# 101_Power.net
KiCad netlist of a schematic drawn in Altium Designer
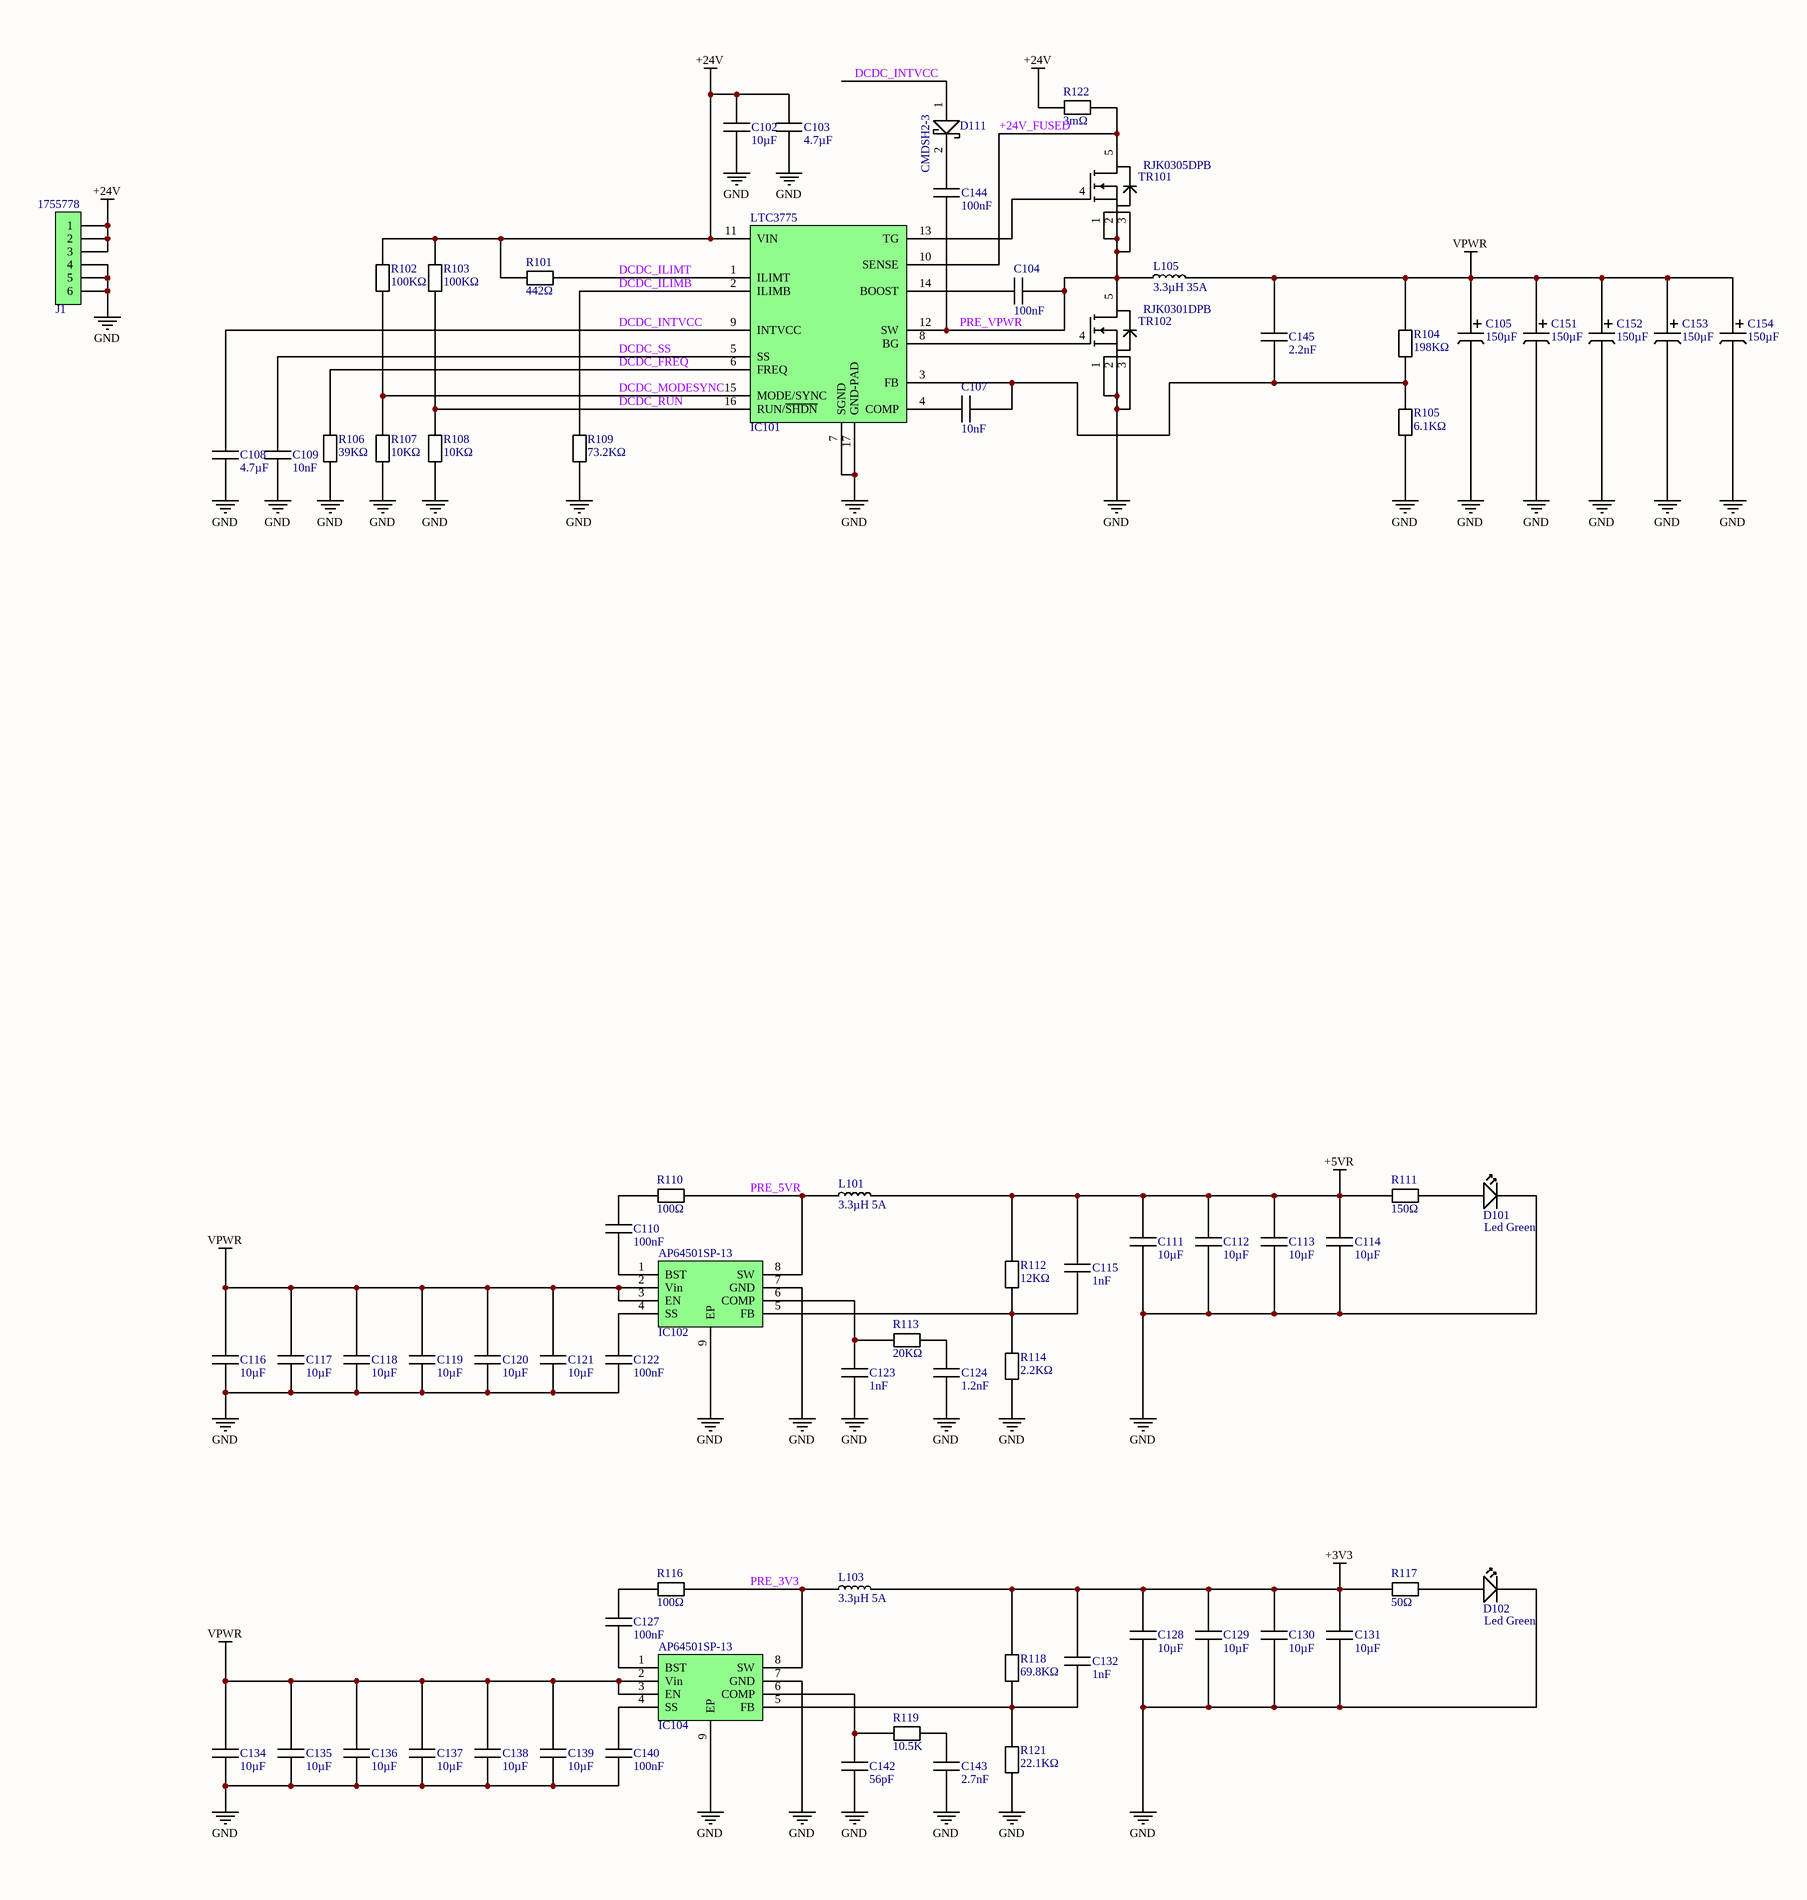
[diagram p0: 101_Power.SchDoc, left]
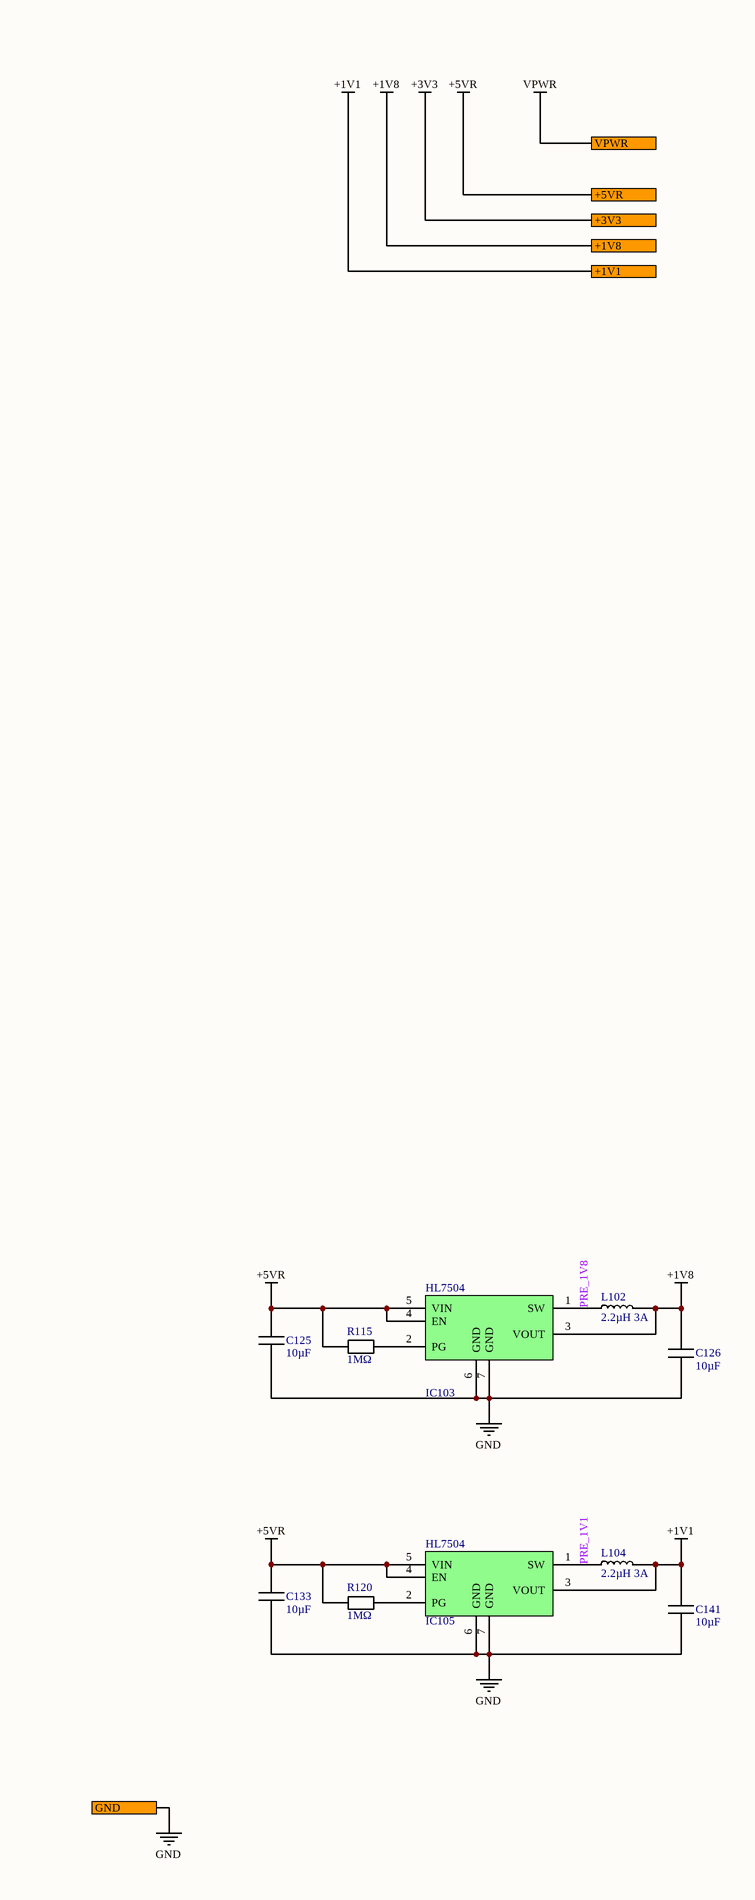
[diagram p1: 101_Power.SchDoc, right]

(export (version "E")
  (design (tool "Eeschema 10.0.6"))
  (components
    (comp (ref "C102")
      (value "10µF")
      (footprint "C1210")
      (description "10µF 63V 10% X7R")
      (fields
        (field (name "REFVAL") "10µF")
        (field (name "PART NUMBER") "CA0024")
        (field (name "MANFACTPART") "GRM32ER71J106KA12")
      )
      (libsource (lib "GTS_Database") (part "C"))
    )
    (comp (ref "C103")
      (value "4.7µF")
      (footprint "C1210")
      (description "4.7µF 100V 10% X5R")
      (fields
        (field (name "REFVAL") "4.7µF")
        (field (name "PART NUMBER") "CA0038")
        (field (name "MANFACTPART") "HMK325BJ475KM-PE")
      )
      (libsource (lib "GTS_Database") (part "C"))
    )
    (comp (ref "C104")
      (value "100nF")
      (footprint "C0402")
      (description "100nF 50V 10% X7R")
      (fields
        (field (name "REFVAL") "100nF")
        (field (name "PART NUMBER") "CA0029")
        (field (name "MANFACTPART") "CGA2B3X7R1H104K050BB")
      )
      (libsource (lib "GTS_Database") (part "C"))
    )
    (comp (ref "C105")
      (value "150µF")
      (footprint "Tantalum_2924_4.1MM")
      (description "150µF 35V 20% 100mΩ")
      (fields
        (field (name "REFVAL") "150µF")
        (field (name "PART NUMBER") "CA0076")
        (field (name "MANFACTPART") "TCJU157M035R0100E")
      )
      (libsource (lib "GTS_Database") (part "C+"))
    )
    (comp (ref "C107")
      (value "10nF")
      (footprint "C0805")
      (description "10nF 50V 10% X7R")
      (fields
        (field (name "REFVAL") "10nF")
        (field (name "PART NUMBER") "CA0021")
        (field (name "MANFACTPART") "C0805C103K5RAC")
      )
      (libsource (lib "GTS_Database") (part "C"))
    )
    (comp (ref "C108")
      (value "4.7µF")
      (footprint "C1210")
      (description "4.7µF 100V 10% X5R")
      (fields
        (field (name "REFVAL") "4.7µF")
        (field (name "PART NUMBER") "CA0038")
        (field (name "MANFACTPART") "HMK325BJ475KM-PE")
      )
      (libsource (lib "GTS_Database") (part "C"))
    )
    (comp (ref "C109")
      (value "10nF")
      (footprint "C0805")
      (description "10nF 50V 10% X7R")
      (fields
        (field (name "REFVAL") "10nF")
        (field (name "PART NUMBER") "CA0021")
        (field (name "MANFACTPART") "C0805C103K5RAC")
      )
      (libsource (lib "GTS_Database") (part "C"))
    )
    (comp (ref "C110")
      (value "100nF")
      (footprint "C0402")
      (description "100nF 50V 10% X7R")
      (fields
        (field (name "REFVAL") "100nF")
        (field (name "PART NUMBER") "CA0029")
        (field (name "MANFACTPART") "CGA2B3X7R1H104K050BB")
      )
      (libsource (lib "GTS_Database") (part "C"))
    )
    (comp (ref "C111")
      (value "10µF")
      (footprint "C0805")
      (description "10µF 16V 10% X5R")
      (fields
        (field (name "REFVAL") "10µF")
        (field (name "PART NUMBER") "CA0001")
        (field (name "MANFACTPART") "GRM21BR61C106KE15L")
      )
      (libsource (lib "GTS_Database") (part "C"))
    )
    (comp (ref "C112")
      (value "10µF")
      (footprint "C0805")
      (description "10µF 16V 10% X5R")
      (fields
        (field (name "REFVAL") "10µF")
        (field (name "PART NUMBER") "CA0001")
        (field (name "MANFACTPART") "GRM21BR61C106KE15L")
      )
      (libsource (lib "GTS_Database") (part "C"))
    )
    (comp (ref "C113")
      (value "10µF")
      (footprint "C0805")
      (description "10µF 16V 10% X5R")
      (fields
        (field (name "REFVAL") "10µF")
        (field (name "PART NUMBER") "CA0001")
        (field (name "MANFACTPART") "GRM21BR61C106KE15L")
      )
      (libsource (lib "GTS_Database") (part "C"))
    )
    (comp (ref "C114")
      (value "10µF")
      (footprint "C0805")
      (description "10µF 16V 10% X5R")
      (fields
        (field (name "REFVAL") "10µF")
        (field (name "PART NUMBER") "CA0001")
        (field (name "MANFACTPART") "GRM21BR61C106KE15L")
      )
      (libsource (lib "GTS_Database") (part "C"))
    )
    (comp (ref "C115")
      (value "1nF")
      (footprint "C0402")
      (description "1nF 50V 1% C0G")
      (fields
        (field (name "REFVAL") "1nF")
        (field (name "PART NUMBER") "CA0031")
        (field (name "MANFACTPART") "GRT1555C1H102FA02D")
      )
      (libsource (lib "GTS_Database") (part "C"))
    )
    (comp (ref "C116")
      (value "10µF")
      (footprint "C0805")
      (description "10µF 35V 10% X5R")
      (fields
        (field (name "REFVAL") "10µF")
        (field (name "PART NUMBER") "CA0005")
        (field (name "MANFACTPART") "C2012X5R1V106K125AC")
      )
      (libsource (lib "GTS_Database") (part "C"))
    )
    (comp (ref "C117")
      (value "10µF")
      (footprint "C0805")
      (description "10µF 35V 10% X5R")
      (fields
        (field (name "REFVAL") "10µF")
        (field (name "PART NUMBER") "CA0005")
        (field (name "MANFACTPART") "C2012X5R1V106K125AC")
      )
      (libsource (lib "GTS_Database") (part "C"))
    )
    (comp (ref "C118")
      (value "10µF")
      (footprint "C0805")
      (description "10µF 35V 10% X5R")
      (fields
        (field (name "REFVAL") "10µF")
        (field (name "PART NUMBER") "CA0005")
        (field (name "MANFACTPART") "C2012X5R1V106K125AC")
      )
      (libsource (lib "GTS_Database") (part "C"))
    )
    (comp (ref "C119")
      (value "10µF")
      (footprint "C0805")
      (description "10µF 35V 10% X5R")
      (fields
        (field (name "REFVAL") "10µF")
        (field (name "PART NUMBER") "CA0005")
        (field (name "MANFACTPART") "C2012X5R1V106K125AC")
      )
      (libsource (lib "GTS_Database") (part "C"))
    )
    (comp (ref "C120")
      (value "10µF")
      (footprint "C0805")
      (description "10µF 35V 10% X5R")
      (fields
        (field (name "REFVAL") "10µF")
        (field (name "PART NUMBER") "CA0005")
        (field (name "MANFACTPART") "C2012X5R1V106K125AC")
      )
      (libsource (lib "GTS_Database") (part "C"))
    )
    (comp (ref "C121")
      (value "10µF")
      (footprint "C0805")
      (description "10µF 35V 10% X5R")
      (fields
        (field (name "REFVAL") "10µF")
        (field (name "PART NUMBER") "CA0005")
        (field (name "MANFACTPART") "C2012X5R1V106K125AC")
      )
      (libsource (lib "GTS_Database") (part "C"))
    )
    (comp (ref "C122")
      (value "100nF")
      (footprint "C0402")
      (description "100nF 50V 10% X7R")
      (fields
        (field (name "REFVAL") "100nF")
        (field (name "PART NUMBER") "CA0029")
        (field (name "MANFACTPART") "CGA2B3X7R1H104K050BB")
      )
      (libsource (lib "GTS_Database") (part "C"))
    )
    (comp (ref "C123")
      (value "1nF")
      (footprint "C0402")
      (description "1nF 50V 1% C0G")
      (fields
        (field (name "REFVAL") "1nF")
        (field (name "PART NUMBER") "CA0031")
        (field (name "MANFACTPART") "GRT1555C1H102FA02D")
      )
      (libsource (lib "GTS_Database") (part "C"))
    )
    (comp (ref "C124")
      (value "1.2nF")
      (footprint "C0402")
      (description "1.2nF 50V 10% X7R")
      (fields
        (field (name "REFVAL") "1.2nF")
        (field (name "PART NUMBER") "CA0030")
        (field (name "MANFACTPART") "GCM155R71H122KA37D")
      )
      (libsource (lib "GTS_Database") (part "C"))
    )
    (comp (ref "C125")
      (value "10µF")
      (footprint "C0603")
      (description "10µF 16V 20% X5R")
      (fields
        (field (name "REFVAL") "10µF")
        (field (name "PART NUMBER") "CA0008")
        (field (name "MANFACTPART") "GRM188R61C106MAALD")
      )
      (libsource (lib "GTS_Database") (part "C"))
    )
    (comp (ref "C126")
      (value "10µF")
      (footprint "C0603")
      (description "10µF 16V 20% X5R")
      (fields
        (field (name "REFVAL") "10µF")
        (field (name "PART NUMBER") "CA0008")
        (field (name "MANFACTPART") "GRM188R61C106MAALD")
      )
      (libsource (lib "GTS_Database") (part "C"))
    )
    (comp (ref "C127")
      (value "100nF")
      (footprint "C0402")
      (description "100nF 50V 10% X7R")
      (fields
        (field (name "REFVAL") "100nF")
        (field (name "PART NUMBER") "CA0029")
        (field (name "MANFACTPART") "CGA2B3X7R1H104K050BB")
      )
      (libsource (lib "GTS_Database") (part "C"))
    )
    (comp (ref "C128")
      (value "10µF")
      (footprint "C0805")
      (description "10µF 16V 10% X5R")
      (fields
        (field (name "REFVAL") "10µF")
        (field (name "PART NUMBER") "CA0001")
        (field (name "MANFACTPART") "GRM21BR61C106KE15L")
      )
      (libsource (lib "GTS_Database") (part "C"))
    )
    (comp (ref "C129")
      (value "10µF")
      (footprint "C0805")
      (description "10µF 16V 10% X5R")
      (fields
        (field (name "REFVAL") "10µF")
        (field (name "PART NUMBER") "CA0001")
        (field (name "MANFACTPART") "GRM21BR61C106KE15L")
      )
      (libsource (lib "GTS_Database") (part "C"))
    )
    (comp (ref "C130")
      (value "10µF")
      (footprint "C0805")
      (description "10µF 16V 10% X5R")
      (fields
        (field (name "REFVAL") "10µF")
        (field (name "PART NUMBER") "CA0001")
        (field (name "MANFACTPART") "GRM21BR61C106KE15L")
      )
      (libsource (lib "GTS_Database") (part "C"))
    )
    (comp (ref "C131")
      (value "10µF")
      (footprint "C0805")
      (description "10µF 16V 10% X5R")
      (fields
        (field (name "REFVAL") "10µF")
        (field (name "PART NUMBER") "CA0001")
        (field (name "MANFACTPART") "GRM21BR61C106KE15L")
      )
      (libsource (lib "GTS_Database") (part "C"))
    )
    (comp (ref "C132")
      (value "1nF")
      (footprint "C0402")
      (description "1nF 50V 1% C0G")
      (fields
        (field (name "REFVAL") "1nF")
        (field (name "PART NUMBER") "CA0031")
        (field (name "MANFACTPART") "GRT1555C1H102FA02D")
      )
      (libsource (lib "GTS_Database") (part "C"))
    )
    (comp (ref "C133")
      (value "10µF")
      (footprint "C0603")
      (description "10µF 16V 20% X5R")
      (fields
        (field (name "REFVAL") "10µF")
        (field (name "PART NUMBER") "CA0008")
        (field (name "MANFACTPART") "GRM188R61C106MAALD")
      )
      (libsource (lib "GTS_Database") (part "C"))
    )
    (comp (ref "C134")
      (value "10µF")
      (footprint "C0805")
      (description "10µF 35V 10% X5R")
      (fields
        (field (name "REFVAL") "10µF")
        (field (name "PART NUMBER") "CA0005")
        (field (name "MANFACTPART") "C2012X5R1V106K125AC")
      )
      (libsource (lib "GTS_Database") (part "C"))
    )
    (comp (ref "C135")
      (value "10µF")
      (footprint "C0805")
      (description "10µF 35V 10% X5R")
      (fields
        (field (name "REFVAL") "10µF")
        (field (name "PART NUMBER") "CA0005")
        (field (name "MANFACTPART") "C2012X5R1V106K125AC")
      )
      (libsource (lib "GTS_Database") (part "C"))
    )
    (comp (ref "C136")
      (value "10µF")
      (footprint "C0805")
      (description "10µF 35V 10% X5R")
      (fields
        (field (name "REFVAL") "10µF")
        (field (name "PART NUMBER") "CA0005")
        (field (name "MANFACTPART") "C2012X5R1V106K125AC")
      )
      (libsource (lib "GTS_Database") (part "C"))
    )
    (comp (ref "C137")
      (value "10µF")
      (footprint "C0805")
      (description "10µF 35V 10% X5R")
      (fields
        (field (name "REFVAL") "10µF")
        (field (name "PART NUMBER") "CA0005")
        (field (name "MANFACTPART") "C2012X5R1V106K125AC")
      )
      (libsource (lib "GTS_Database") (part "C"))
    )
    (comp (ref "C138")
      (value "10µF")
      (footprint "C0805")
      (description "10µF 35V 10% X5R")
      (fields
        (field (name "REFVAL") "10µF")
        (field (name "PART NUMBER") "CA0005")
        (field (name "MANFACTPART") "C2012X5R1V106K125AC")
      )
      (libsource (lib "GTS_Database") (part "C"))
    )
    (comp (ref "C139")
      (value "10µF")
      (footprint "C0805")
      (description "10µF 35V 10% X5R")
      (fields
        (field (name "REFVAL") "10µF")
        (field (name "PART NUMBER") "CA0005")
        (field (name "MANFACTPART") "C2012X5R1V106K125AC")
      )
      (libsource (lib "GTS_Database") (part "C"))
    )
    (comp (ref "C140")
      (value "100nF")
      (footprint "C0402")
      (description "100nF 50V 10% X7R")
      (fields
        (field (name "REFVAL") "100nF")
        (field (name "PART NUMBER") "CA0029")
        (field (name "MANFACTPART") "CGA2B3X7R1H104K050BB")
      )
      (libsource (lib "GTS_Database") (part "C"))
    )
    (comp (ref "C141")
      (value "10µF")
      (footprint "C0603")
      (description "10µF 16V 20% X5R")
      (fields
        (field (name "REFVAL") "10µF")
        (field (name "PART NUMBER") "CA0008")
        (field (name "MANFACTPART") "GRM188R61C106MAALD")
      )
      (libsource (lib "GTS_Database") (part "C"))
    )
    (comp (ref "C142")
      (value "56pF")
      (footprint "C0402")
      (description "56pF 50V 2% C0G")
      (fields
        (field (name "REFVAL") "56pF")
        (field (name "PART NUMBER") "CA0068")
        (field (name "MANFACTPART") "CC0402GRNPO9BN560")
      )
      (libsource (lib "GTS_Database") (part "C"))
    )
    (comp (ref "C143")
      (value "2.7nF")
      (footprint "C0402")
      (description "2.7nF 50V 5% X7R")
      (fields
        (field (name "REFVAL") "2.7nF")
        (field (name "PART NUMBER") "CA0055")
        (field (name "MANFACTPART") "GRM155R71H272JA01D")
      )
      (libsource (lib "GTS_Database") (part "C"))
    )
    (comp (ref "C144")
      (value "100nF")
      (footprint "C0402")
      (description "100nF 50V 10% X7R")
      (fields
        (field (name "REFVAL") "100nF")
        (field (name "PART NUMBER") "CA0029")
        (field (name "MANFACTPART") "CGA2B3X7R1H104K050BB")
      )
      (libsource (lib "GTS_Database") (part "C"))
    )
    (comp (ref "C145")
      (value "2.2nF")
      (footprint "C0805")
      (description "2.2nF 50V 10% X7R")
      (fields
        (field (name "REFVAL") "2.2nF")
        (field (name "PART NUMBER") "CA0070")
        (field (name "MANFACTPART") "C0805C222K5RAC")
      )
      (libsource (lib "GTS_Database") (part "C"))
    )
    (comp (ref "C151")
      (value "150µF")
      (footprint "Tantalum_2924_4.1MM")
      (description "150µF 35V 20% 100mΩ")
      (fields
        (field (name "REFVAL") "150µF")
        (field (name "PART NUMBER") "CA0076")
        (field (name "MANFACTPART") "TCJU157M035R0100E")
      )
      (libsource (lib "GTS_Database") (part "C+"))
    )
    (comp (ref "C152")
      (value "150µF")
      (footprint "Tantalum_2924_4.1MM")
      (description "150µF 35V 20% 100mΩ")
      (fields
        (field (name "REFVAL") "150µF")
        (field (name "PART NUMBER") "CA0076")
        (field (name "MANFACTPART") "TCJU157M035R0100E")
      )
      (libsource (lib "GTS_Database") (part "C+"))
    )
    (comp (ref "C153")
      (value "150µF")
      (footprint "Tantalum_2924_4.1MM")
      (description "150µF 35V 20% 100mΩ")
      (fields
        (field (name "REFVAL") "150µF")
        (field (name "PART NUMBER") "CA0076")
        (field (name "MANFACTPART") "TCJU157M035R0100E")
      )
      (libsource (lib "GTS_Database") (part "C+"))
    )
    (comp (ref "C154")
      (value "150µF")
      (footprint "Tantalum_2924_4.1MM")
      (description "150µF 35V 20% 100mΩ")
      (fields
        (field (name "REFVAL") "150µF")
        (field (name "PART NUMBER") "CA0076")
        (field (name "MANFACTPART") "TCJU157M035R0100E")
      )
      (libsource (lib "GTS_Database") (part "C+"))
    )
    (comp (ref "D101")
      (value "Led Green")
      (footprint "Led0805")
      (fields
        (field (name "REFVAL") "Led Green")
        (field (name "PART NUMBER") "DI0001")
        (field (name "MANFACTPART") "KP-2012CGCK")
      )
      (libsource (lib "GTS_Database") (part "Led"))
    )
    (comp (ref "D102")
      (value "Led Green")
      (footprint "Led0805")
      (fields
        (field (name "REFVAL") "Led Green")
        (field (name "PART NUMBER") "DI0001")
        (field (name "MANFACTPART") "KP-2012CGCK")
      )
      (libsource (lib "GTS_Database") (part "Led"))
    )
    (comp (ref "D111")
      (value "CMDSH2-3")
      (footprint "SOD-323")
      (description "Schottky Diodes 30V")
      (fields
        (field (name "REFVAL") "CMDSH2-3")
        (field (name "PART NUMBER") "DI0013")
        (field (name "MANFACTPART") "CMDSH2-3 TR PBFREE")
      )
      (libsource (lib "GTS_Database") (part "Dschottky"))
    )
    (comp (ref "IC101")
      (value "LTC3775")
      (footprint "QFN-16G_3X3")
      (description "High Frequency Synchronous Step-Down Voltage Mode DC/DC Controller")
      (fields
        (field (name "REFVAL") "LTC3775")
        (field (name "PART NUMBER") "IC0063")
        (field (name "MANFACTPART") "LTC3775IUD#PBF")
      )
      (libsource (lib "GTS_Database") (part "LTC3775"))
    )
    (comp (ref "IC102")
      (value "AP64501SP-13")
      (footprint "SO-8-EP")
      (description "3.8V TO 40V INPUT, 5A LOW IQ SYNCHRONOUS BUCK WITH PROGRAMMABLE SOFT-START TIME")
      (fields (field (name "REFVAL") "AP64501SP-13") (field (name "PART NUMBER") "IC0031"))
      (libsource (lib "GTS_Database") (part "AP645"))
    )
    (comp (ref "IC103")
      (value "HL7504")
      (footprint "DFN-6G_2X2")
      (description "3MHz 2A Buck Converter 1.80V OUT")
      (fields
        (field (name "REFVAL") "HL7504")
        (field (name "PART NUMBER") "IC0064")
        (field (name "MANFACTPART") "HL7504FN07")
      )
      (libsource (lib "GTS_Database") (part "HL7504"))
    )
    (comp (ref "IC104")
      (value "AP64501SP-13")
      (footprint "SO-8-EP")
      (description "3.8V TO 40V INPUT, 5A LOW IQ SYNCHRONOUS BUCK WITH PROGRAMMABLE SOFT-START TIME")
      (fields (field (name "REFVAL") "AP64501SP-13") (field (name "PART NUMBER") "IC0031"))
      (libsource (lib "GTS_Database") (part "AP645"))
    )
    (comp (ref "IC105")
      (value "HL7504")
      (footprint "DFN-6G_2X2")
      (description "3MHz 2A Buck Converter 1.10V OUT")
      (fields
        (field (name "REFVAL") "HL7504")
        (field (name "PART NUMBER") "IC0050")
        (field (name "MANFACTPART") "HL7504FN08")
      )
      (libsource (lib "GTS_Database") (part "HL7504"))
    )
    (comp (ref "J1")
      (value "1755778")
      (footprint "1755778")
      (description "Pluggable Terminal Blocks 6 Pos 5.08mm pitch Through Hole Header")
      (fields (field (name "REFVAL") "1755778") (field (name "PART NUMBER") "CO0033"))
      (libsource (lib "GTS_Database") (part "CONN1X6P"))
    )
    (comp (ref "L101")
      (value "3.3µH 5A")
      (footprint "SRN6045TA")
      (description "3.3µH 5A 30% 21mΩ")
      (fields
        (field (name "REFVAL") "3.3µH 5A")
        (field (name "PART NUMBER") "IN0005")
        (field (name "MANFACTPART") "SRN6045TA-3R3Y")
      )
      (libsource (lib "GTS_Database") (part "L"))
    )
    (comp (ref "L102")
      (value "2.2µH 3A")
      (footprint "NRS4018")
      (fields
        (field (name "REFVAL") "2.2µH 3A")
        (field (name "PART NUMBER") "IN0004")
        (field (name "MANFACTPART") "NRS4018T2R2MDGJ")
      )
      (libsource (lib "GTS_Database") (part "L"))
    )
    (comp (ref "L103")
      (value "3.3µH 5A")
      (footprint "SRN6045TA")
      (description "3.3µH 5A 30% 21mΩ")
      (fields
        (field (name "REFVAL") "3.3µH 5A")
        (field (name "PART NUMBER") "IN0005")
        (field (name "MANFACTPART") "SRN6045TA-3R3Y")
      )
      (libsource (lib "GTS_Database") (part "L"))
    )
    (comp (ref "L104")
      (value "2.2µH 3A")
      (footprint "NRS4018")
      (fields
        (field (name "REFVAL") "2.2µH 3A")
        (field (name "PART NUMBER") "IN0004")
        (field (name "MANFACTPART") "NRS4018T2R2MDGJ")
      )
      (libsource (lib "GTS_Database") (part "L"))
    )
    (comp (ref "L105")
      (value "3.3µH 35A")
      (footprint "IN-2P_17X17")
      (description "3.3µH 35A 20% 2.93mΩ")
      (fields
        (field (name "REFVAL") "3.3µH 35A")
        (field (name "PART NUMBER") "IN0018")
        (field (name "MANFACTPART") "IHLP6767GZER3R3M11")
      )
      (libsource (lib "GTS_Database") (part "L"))
    )
    (comp (ref "R101")
      (value "442Ω")
      (footprint "R0402")
      (description "442Ω 1% 100mW 100PPM")
      (fields
        (field (name "REFVAL") "442Ω")
        (field (name "PART NUMBER") "RS0083")
        (field (name "MANFACTPART") "ERJ-2RKF4420X")
      )
      (libsource (lib "GTS_Database") (part "R"))
    )
    (comp (ref "R102")
      (value "100KΩ")
      (footprint "R0402")
      (description "100KΩ 1% 62.5mW 100PPM")
      (fields
        (field (name "REFVAL") "100KΩ")
        (field (name "PART NUMBER") "RS0036")
        (field (name "MANFACTPART") "AC0402FR-13100KL")
      )
      (libsource (lib "GTS_Database") (part "R"))
    )
    (comp (ref "R103")
      (value "100KΩ")
      (footprint "R0402")
      (description "100KΩ 1% 62.5mW 100PPM")
      (fields
        (field (name "REFVAL") "100KΩ")
        (field (name "PART NUMBER") "RS0036")
        (field (name "MANFACTPART") "AC0402FR-13100KL")
      )
      (libsource (lib "GTS_Database") (part "R"))
    )
    (comp (ref "R104")
      (value "198KΩ")
      (footprint "R0603")
      (description "198KΩ 0.1% 100mW 25PPM")
      (fields
        (field (name "REFVAL") "198KΩ")
        (field (name "PART NUMBER") "RS0088")
        (field (name "MANFACTPART") "RT0603BRD07198KL")
      )
      (libsource (lib "GTS_Database") (part "R"))
    )
    (comp (ref "R105")
      (value "6.1KΩ")
      (footprint "R0402")
      (description "6.1KΩ 0.1% 100mW 25PPM")
      (fields
        (field (name "REFVAL") "6.1KΩ")
        (field (name "PART NUMBER") "RS0084")
        (field (name "MANFACTPART") "TNPW040236K1BEED")
      )
      (libsource (lib "GTS_Database") (part "R"))
    )
    (comp (ref "R106")
      (value "39KΩ")
      (footprint "R0402")
      (description "39KΩ 1% 62.5mW 100PPM")
      (fields
        (field (name "REFVAL") "39KΩ")
        (field (name "PART NUMBER") "RS0089")
        (field (name "MANFACTPART") "CRG0402F39K")
      )
      (libsource (lib "GTS_Database") (part "R"))
    )
    (comp (ref "R107")
      (value "10KΩ")
      (footprint "R0402")
      (description "10KΩ 1% 62.5mW")
      (fields
        (field (name "REFVAL") "10KΩ")
        (field (name "PART NUMBER") "RS0011")
        (field (name "MANFACTPART") "WR04X1002FTL")
      )
      (libsource (lib "GTS_Database") (part "R"))
    )
    (comp (ref "R108")
      (value "10KΩ")
      (footprint "R0402")
      (description "10KΩ 1% 62.5mW")
      (fields
        (field (name "REFVAL") "10KΩ")
        (field (name "PART NUMBER") "RS0011")
        (field (name "MANFACTPART") "WR04X1002FTL")
      )
      (libsource (lib "GTS_Database") (part "R"))
    )
    (comp (ref "R109")
      (value "73.2KΩ")
      (footprint "R0402")
      (description "73.2KΩ 1% 100mW 100PPM")
      (fields
        (field (name "REFVAL") "73.2KΩ")
        (field (name "PART NUMBER") "RS0090")
        (field (name "MANFACTPART") "RK73H1ETTP7322F")
      )
      (libsource (lib "GTS_Database") (part "R"))
    )
    (comp (ref "R110")
      (value "100Ω")
      (footprint "R0603")
      (description "100Ω 1% 100mW")
      (fields
        (field (name "REFVAL") "100Ω")
        (field (name "PART NUMBER") "RS0007")
        (field (name "MANFACTPART") "WR06X1000FTL")
      )
      (libsource (lib "GTS_Database") (part "R"))
    )
    (comp (ref "R111")
      (value "150Ω")
      (footprint "R0603")
      (description "150Ω 1% 100mW")
      (fields
        (field (name "REFVAL") "150Ω")
        (field (name "PART NUMBER") "RS0001")
        (field (name "MANFACTPART") "MCWR06X1500FTL")
      )
      (libsource (lib "GTS_Database") (part "R"))
    )
    (comp (ref "R112")
      (value "12KΩ")
      (footprint "R0402")
      (description "12KΩ 1% 62.5mW")
      (fields
        (field (name "REFVAL") "12KΩ")
        (field (name "PART NUMBER") "RS0015")
        (field (name "MANFACTPART") "RC0402FR-1312KL")
      )
      (libsource (lib "GTS_Database") (part "R"))
    )
    (comp (ref "R113")
      (value "20KΩ")
      (footprint "R0402")
      (description "20KΩ 1% 100mW 100PPM")
      (fields
        (field (name "REFVAL") "20KΩ")
        (field (name "PART NUMBER") "RS0034")
        (field (name "MANFACTPART") "ERJ-S02F2002X")
      )
      (libsource (lib "GTS_Database") (part "R"))
    )
    (comp (ref "R114")
      (value "2.2KΩ")
      (footprint "R0402")
      (description "2.2KΩ 1% 62.5mW 100PPM")
      (fields
        (field (name "REFVAL") "2.2KΩ")
        (field (name "PART NUMBER") "RS0035")
        (field (name "MANFACTPART") "CRGCQ0402F2K2")
      )
      (libsource (lib "GTS_Database") (part "R"))
    )
    (comp (ref "R115")
      (value "1MΩ")
      (footprint "R0402")
      (description "1MΩ 1% 62.5mW 100PPM")
      (fields
        (field (name "REFVAL") "1MΩ")
        (field (name "PART NUMBER") "RS0066")
        (field (name "MANFACTPART") "0402WGF1004TCE")
      )
      (libsource (lib "GTS_Database") (part "R"))
    )
    (comp (ref "R116")
      (value "100Ω")
      (footprint "R0603")
      (description "100Ω 1% 100mW")
      (fields
        (field (name "REFVAL") "100Ω")
        (field (name "PART NUMBER") "RS0007")
        (field (name "MANFACTPART") "WR06X1000FTL")
      )
      (libsource (lib "GTS_Database") (part "R"))
    )
    (comp (ref "R117")
      (value "50Ω")
      (footprint "R0603")
      (description "50Ω 0.1% 100mW 50PPM")
      (fields
        (field (name "REFVAL") "50Ω")
        (field (name "PART NUMBER") "RS0080")
        (field (name "MANFACTPART") "RT0603BRE0750RL")
      )
      (libsource (lib "GTS_Database") (part "R"))
    )
    (comp (ref "R118")
      (value "69.8KΩ")
      (footprint "R0603")
      (description "69.8KΩ 1% 100mW 100PPM")
      (fields
        (field (name "REFVAL") "69.8KΩ")
        (field (name "PART NUMBER") "RS0041")
        (field (name "MANFACTPART") "CRCW060369K8FKEB")
      )
      (libsource (lib "GTS_Database") (part "R"))
    )
    (comp (ref "R119")
      (value "10.5K")
      (footprint "R0402")
      (description "10.5KΩ 1% 62.5mW 100PPM")
      (fields
        (field (name "REFVAL") "10.5K")
        (field (name "PART NUMBER") "RS0054")
        (field (name "MANFACTPART") "CRCW040210K5FKEDC")
      )
      (libsource (lib "GTS_Database") (part "R"))
    )
    (comp (ref "R120")
      (value "1MΩ")
      (footprint "R0402")
      (description "1MΩ 1% 62.5mW 100PPM")
      (fields
        (field (name "REFVAL") "1MΩ")
        (field (name "PART NUMBER") "RS0066")
        (field (name "MANFACTPART") "0402WGF1004TCE")
      )
      (libsource (lib "GTS_Database") (part "R"))
    )
    (comp (ref "R121")
      (value "22.1KΩ")
      (footprint "R0603")
      (description "22.1KΩ 1% 100mW 100PPM")
      (fields
        (field (name "REFVAL") "22.1KΩ")
        (field (name "PART NUMBER") "RS0040")
        (field (name "MANFACTPART") "RC0603FR-0722K1L")
      )
      (libsource (lib "GTS_Database") (part "R"))
    )
    (comp (ref "R122")
      (value "3mΩ")
      (footprint "R1206")
      (description "3mΩ 5% 250mW 100PPM")
      (fields
        (field (name "REFVAL") "3mΩ")
        (field (name "PART NUMBER") "RS0091")
        (field (name "MANFACTPART") "AC1206JR-073ML")
      )
      (libsource (lib "GTS_Database") (part "R"))
    )
    (comp (ref "TR101")
      (value "RJK0305DPB")
      (footprint "LFPAK-5_4.9X4")
      (description "30V/8mΩ, N-channel Power MOSFET, 30A")
      (fields (field (name "REFVAL") "RJK0305DPB") (field (name "PART NUMBER") "TR0015"))
      (libsource (lib "GTS_Database") (part "MOS_E_N_4G5D123S"))
    )
    (comp (ref "TR102")
      (value "RJK0301DPB")
      (footprint "LFPAK-5_4.9X4")
      (description "30V/2.8mΩ, N-channel Power MOSFET, 60A")
      (fields (field (name "REFVAL") "RJK0301DPB") (field (name "PART NUMBER") "TR0014"))
      (libsource (lib "GTS_Database") (part "MOS_E_N_4G5D123S"))
    )
  )
  (nets
    (net (code "1") (name "+1V1") (class "Default")
      (node (ref "C141") (pin "1") (pinfunction "1_1") (pintype "passive"))
      (node (ref "IC105") (pin "3") (pinfunction "VOUT_3") (pintype "passive"))
      (node (ref "L104") (pin "2") (pinfunction "2_2") (pintype "passive"))
    )
    (net (code "2") (name "+1V8") (class "Default")
      (node (ref "C126") (pin "1") (pinfunction "1_1") (pintype "passive"))
      (node (ref "IC103") (pin "3") (pinfunction "VOUT_3") (pintype "passive"))
      (node (ref "L102") (pin "2") (pinfunction "2_2") (pintype "passive"))
    )
    (net (code "3") (name "+3V3") (class "Default")
      (node (ref "C128") (pin "1") (pinfunction "1_1") (pintype "passive"))
      (node (ref "C129") (pin "1") (pinfunction "1_1") (pintype "passive"))
      (node (ref "C130") (pin "1") (pinfunction "1_1") (pintype "passive"))
      (node (ref "C131") (pin "1") (pinfunction "1_1") (pintype "passive"))
      (node (ref "C132") (pin "1") (pinfunction "1_1") (pintype "passive"))
      (node (ref "L103") (pin "2") (pinfunction "2_2") (pintype "passive"))
      (node (ref "R117") (pin "1") (pinfunction "1_1") (pintype "passive"))
      (node (ref "R118") (pin "2") (pinfunction "2_2") (pintype "passive"))
    )
    (net (code "4") (name "+5VR") (class "Default")
      (node (ref "C111") (pin "1") (pinfunction "1_1") (pintype "passive"))
      (node (ref "C112") (pin "1") (pinfunction "1_1") (pintype "passive"))
      (node (ref "C113") (pin "1") (pinfunction "1_1") (pintype "passive"))
      (node (ref "C114") (pin "1") (pinfunction "1_1") (pintype "passive"))
      (node (ref "C115") (pin "1") (pinfunction "1_1") (pintype "passive"))
      (node (ref "C125") (pin "1") (pinfunction "1_1") (pintype "passive"))
      (node (ref "C133") (pin "1") (pinfunction "1_1") (pintype "passive"))
      (node (ref "IC103") (pin "4") (pinfunction "EN_4") (pintype "passive"))
      (node (ref "IC103") (pin "5") (pinfunction "VIN_5") (pintype "passive"))
      (node (ref "IC105") (pin "4") (pinfunction "EN_4") (pintype "passive"))
      (node (ref "IC105") (pin "5") (pinfunction "VIN_5") (pintype "passive"))
      (node (ref "L101") (pin "2") (pinfunction "2_2") (pintype "passive"))
      (node (ref "R111") (pin "1") (pinfunction "1_1") (pintype "passive"))
      (node (ref "R112") (pin "2") (pinfunction "2_2") (pintype "passive"))
      (node (ref "R115") (pin "1") (pinfunction "1_1") (pintype "passive"))
      (node (ref "R120") (pin "1") (pinfunction "1_1") (pintype "passive"))
    )
    (net (code "5") (name "+24V") (class "Default")
      (node (ref "C102") (pin "1") (pinfunction "1_1") (pintype "passive"))
      (node (ref "C103") (pin "1") (pinfunction "1_1") (pintype "passive"))
      (node (ref "IC101") (pin "11") (pinfunction "VIN_11") (pintype "passive"))
      (node (ref "J1") (pin "1") (pinfunction "1_1") (pintype "passive"))
      (node (ref "J1") (pin "2") (pinfunction "2_2") (pintype "passive"))
      (node (ref "J1") (pin "3") (pinfunction "3_3") (pintype "passive"))
      (node (ref "R101") (pin "2") (pinfunction "2_2") (pintype "passive"))
      (node (ref "R102") (pin "2") (pinfunction "2_2") (pintype "passive"))
      (node (ref "R103") (pin "2") (pinfunction "2_2") (pintype "passive"))
      (node (ref "R122") (pin "1") (pinfunction "1_1") (pintype "passive"))
    )
    (net (code "6") (name "/+24V_FUSED") (class "Default")
      (node (ref "IC101") (pin "10") (pinfunction "SENSE_10") (pintype "passive"))
      (node (ref "R122") (pin "2") (pinfunction "2_2") (pintype "passive"))
      (node (ref "TR101") (pin "5") (pinfunction "D_5") (pintype "passive"))
    )
    (net (code "7") (name "/DCDC_FREQ") (class "Default")
      (node (ref "IC101") (pin "6") (pinfunction "FREQ_6") (pintype "passive"))
      (node (ref "R106") (pin "2") (pinfunction "2_2") (pintype "passive"))
    )
    (net (code "8") (name "/DCDC_ILIMB") (class "Default")
      (node (ref "IC101") (pin "2") (pinfunction "ILIMB_2") (pintype "passive"))
      (node (ref "R109") (pin "2") (pinfunction "2_2") (pintype "passive"))
    )
    (net (code "9") (name "/DCDC_ILIMT") (class "Default")
      (node (ref "IC101") (pin "1") (pinfunction "ILIMT_1") (pintype "passive"))
      (node (ref "R101") (pin "1") (pinfunction "1_1") (pintype "passive"))
    )
    (net (code "10") (name "/DCDC_INTVCC") (class "Default")
      (node (ref "C108") (pin "1") (pinfunction "1_1") (pintype "passive"))
      (node (ref "D111") (pin "1") (pinfunction "A_1") (pintype "passive"))
      (node (ref "IC101") (pin "9") (pinfunction "INTVCC_9") (pintype "passive"))
    )
    (net (code "11") (name "/DCDC_MODESYNC") (class "Default")
      (node (ref "IC101") (pin "15") (pinfunction "MODE/SYNC_15") (pintype "passive"))
      (node (ref "R102") (pin "1") (pinfunction "1_1") (pintype "passive"))
      (node (ref "R107") (pin "2") (pinfunction "2_2") (pintype "passive"))
    )
    (net (code "12") (name "/DCDC_RUN") (class "Default")
      (node (ref "IC101") (pin "16") (pinfunction "RUN/~{SHDN}_16") (pintype "passive"))
      (node (ref "R103") (pin "1") (pinfunction "1_1") (pintype "passive"))
      (node (ref "R108") (pin "2") (pinfunction "2_2") (pintype "passive"))
    )
    (net (code "13") (name "/DCDC_SS") (class "Default")
      (node (ref "C109") (pin "1") (pinfunction "1_1") (pintype "passive"))
      (node (ref "IC101") (pin "5") (pinfunction "SS_5") (pintype "passive"))
    )
    (net (code "14") (name "/PRE_1V1") (class "Default")
      (node (ref "IC105") (pin "1") (pinfunction "SW_1") (pintype "passive"))
      (node (ref "L104") (pin "1") (pinfunction "1_1") (pintype "passive"))
    )
    (net (code "15") (name "/PRE_1V8") (class "Default")
      (node (ref "IC103") (pin "1") (pinfunction "SW_1") (pintype "passive"))
      (node (ref "L102") (pin "1") (pinfunction "1_1") (pintype "passive"))
    )
    (net (code "16") (name "/PRE_3V3") (class "Default")
      (node (ref "IC104") (pin "8") (pinfunction "SW_8") (pintype "passive"))
      (node (ref "L103") (pin "1") (pinfunction "1_1") (pintype "passive"))
      (node (ref "R116") (pin "2") (pinfunction "2_2") (pintype "passive"))
    )
    (net (code "17") (name "/PRE_5VR") (class "Default")
      (node (ref "IC102") (pin "8") (pinfunction "SW_8") (pintype "passive"))
      (node (ref "L101") (pin "1") (pinfunction "1_1") (pintype "passive"))
      (node (ref "R110") (pin "2") (pinfunction "2_2") (pintype "passive"))
    )
    (net (code "18") (name "/PRE_VPWR") (class "Default")
      (node (ref "C104") (pin "2") (pinfunction "2_2") (pintype "passive"))
      (node (ref "C144") (pin "2") (pinfunction "2_2") (pintype "passive"))
      (node (ref "IC101") (pin "12") (pinfunction "SW_12") (pintype "passive"))
      (node (ref "L105") (pin "1") (pinfunction "1_1") (pintype "passive"))
      (node (ref "TR101") (pin "1") (pinfunction "S_1") (pintype "passive"))
      (node (ref "TR101") (pin "2") (pinfunction "S_2") (pintype "passive"))
      (node (ref "TR101") (pin "3") (pinfunction "S_3") (pintype "passive"))
      (node (ref "TR102") (pin "5") (pinfunction "D_5") (pintype "passive"))
    )
    (net (code "19") (name "GND") (class "Default")
      (node (ref "C102") (pin "2") (pinfunction "2_2") (pintype "passive"))
      (node (ref "C103") (pin "2") (pinfunction "2_2") (pintype "passive"))
      (node (ref "C105") (pin "2") (pinfunction "2_2") (pintype "passive"))
      (node (ref "C108") (pin "2") (pinfunction "2_2") (pintype "passive"))
      (node (ref "C109") (pin "2") (pinfunction "2_2") (pintype "passive"))
      (node (ref "C111") (pin "2") (pinfunction "2_2") (pintype "passive"))
      (node (ref "C112") (pin "2") (pinfunction "2_2") (pintype "passive"))
      (node (ref "C113") (pin "2") (pinfunction "2_2") (pintype "passive"))
      (node (ref "C114") (pin "2") (pinfunction "2_2") (pintype "passive"))
      (node (ref "C116") (pin "2") (pinfunction "2_2") (pintype "passive"))
      (node (ref "C117") (pin "2") (pinfunction "2_2") (pintype "passive"))
      (node (ref "C118") (pin "2") (pinfunction "2_2") (pintype "passive"))
      (node (ref "C119") (pin "2") (pinfunction "2_2") (pintype "passive"))
      (node (ref "C120") (pin "2") (pinfunction "2_2") (pintype "passive"))
      (node (ref "C121") (pin "2") (pinfunction "2_2") (pintype "passive"))
      (node (ref "C122") (pin "2") (pinfunction "2_2") (pintype "passive"))
      (node (ref "C123") (pin "2") (pinfunction "2_2") (pintype "passive"))
      (node (ref "C124") (pin "2") (pinfunction "2_2") (pintype "passive"))
      (node (ref "C125") (pin "2") (pinfunction "2_2") (pintype "passive"))
      (node (ref "C126") (pin "2") (pinfunction "2_2") (pintype "passive"))
      (node (ref "C128") (pin "2") (pinfunction "2_2") (pintype "passive"))
      (node (ref "C129") (pin "2") (pinfunction "2_2") (pintype "passive"))
      (node (ref "C130") (pin "2") (pinfunction "2_2") (pintype "passive"))
      (node (ref "C131") (pin "2") (pinfunction "2_2") (pintype "passive"))
      (node (ref "C133") (pin "2") (pinfunction "2_2") (pintype "passive"))
      (node (ref "C134") (pin "2") (pinfunction "2_2") (pintype "passive"))
      (node (ref "C135") (pin "2") (pinfunction "2_2") (pintype "passive"))
      (node (ref "C136") (pin "2") (pinfunction "2_2") (pintype "passive"))
      (node (ref "C137") (pin "2") (pinfunction "2_2") (pintype "passive"))
      (node (ref "C138") (pin "2") (pinfunction "2_2") (pintype "passive"))
      (node (ref "C139") (pin "2") (pinfunction "2_2") (pintype "passive"))
      (node (ref "C140") (pin "2") (pinfunction "2_2") (pintype "passive"))
      (node (ref "C141") (pin "2") (pinfunction "2_2") (pintype "passive"))
      (node (ref "C142") (pin "2") (pinfunction "2_2") (pintype "passive"))
      (node (ref "C143") (pin "2") (pinfunction "2_2") (pintype "passive"))
      (node (ref "C151") (pin "2") (pinfunction "2_2") (pintype "passive"))
      (node (ref "C152") (pin "2") (pinfunction "2_2") (pintype "passive"))
      (node (ref "C153") (pin "2") (pinfunction "2_2") (pintype "passive"))
      (node (ref "C154") (pin "2") (pinfunction "2_2") (pintype "passive"))
      (node (ref "D101") (pin "K") (pinfunction "K_K") (pintype "passive"))
      (node (ref "D102") (pin "K") (pinfunction "K_K") (pintype "passive"))
      (node (ref "IC101") (pin "17") (pinfunction "GND-PAD_17") (pintype "passive"))
      (node (ref "IC101") (pin "7") (pinfunction "SGND_7") (pintype "passive"))
      (node (ref "IC102") (pin "7") (pinfunction "GND_7") (pintype "passive"))
      (node (ref "IC102") (pin "9") (pinfunction "EP_9") (pintype "passive"))
      (node (ref "IC103") (pin "6") (pinfunction "GND_6") (pintype "passive"))
      (node (ref "IC103") (pin "7") (pinfunction "GND_7") (pintype "passive"))
      (node (ref "IC104") (pin "7") (pinfunction "GND_7") (pintype "passive"))
      (node (ref "IC104") (pin "9") (pinfunction "EP_9") (pintype "passive"))
      (node (ref "IC105") (pin "6") (pinfunction "GND_6") (pintype "passive"))
      (node (ref "IC105") (pin "7") (pinfunction "GND_7") (pintype "passive"))
      (node (ref "J1") (pin "4") (pinfunction "4_4") (pintype "passive"))
      (node (ref "J1") (pin "5") (pinfunction "5_5") (pintype "passive"))
      (node (ref "J1") (pin "6") (pinfunction "6_6") (pintype "passive"))
      (node (ref "R105") (pin "1") (pinfunction "1_1") (pintype "passive"))
      (node (ref "R106") (pin "1") (pinfunction "1_1") (pintype "passive"))
      (node (ref "R107") (pin "1") (pinfunction "1_1") (pintype "passive"))
      (node (ref "R108") (pin "1") (pinfunction "1_1") (pintype "passive"))
      (node (ref "R109") (pin "1") (pinfunction "1_1") (pintype "passive"))
      (node (ref "R114") (pin "1") (pinfunction "1_1") (pintype "passive"))
      (node (ref "R121") (pin "1") (pinfunction "1_1") (pintype "passive"))
      (node (ref "TR102") (pin "1") (pinfunction "S_1") (pintype "passive"))
      (node (ref "TR102") (pin "2") (pinfunction "S_2") (pintype "passive"))
      (node (ref "TR102") (pin "3") (pinfunction "S_3") (pintype "passive"))
    )
    (net (code "20") (name "Net-(C110-Pad1)") (class "Default")
      (node (ref "C110") (pin "1") (pinfunction "1_1") (pintype "passive"))
      (node (ref "R110") (pin "1") (pinfunction "1_1") (pintype "passive"))
    )
    (net (code "21") (name "Net-(C124-Pad1)") (class "Default")
      (node (ref "C124") (pin "1") (pinfunction "1_1") (pintype "passive"))
      (node (ref "R113") (pin "1") (pinfunction "1_1") (pintype "passive"))
    )
    (net (code "22") (name "Net-(C127-Pad1)") (class "Default")
      (node (ref "C127") (pin "1") (pinfunction "1_1") (pintype "passive"))
      (node (ref "R116") (pin "1") (pinfunction "1_1") (pintype "passive"))
    )
    (net (code "23") (name "Net-(C143-Pad1)") (class "Default")
      (node (ref "C143") (pin "1") (pinfunction "1_1") (pintype "passive"))
      (node (ref "R119") (pin "1") (pinfunction "1_1") (pintype "passive"))
    )
    (net (code "24") (name "Net-(D101-PadA)") (class "Default")
      (node (ref "D101") (pin "A") (pinfunction "A_A") (pintype "passive"))
      (node (ref "R111") (pin "2") (pinfunction "2_2") (pintype "passive"))
    )
    (net (code "25") (name "Net-(D102-PadA)") (class "Default")
      (node (ref "D102") (pin "A") (pinfunction "A_A") (pintype "passive"))
      (node (ref "R117") (pin "2") (pinfunction "2_2") (pintype "passive"))
    )
    (net (code "26") (name "Net-(D111-K)") (class "Default")
      (node (ref "C144") (pin "1") (pinfunction "1_1") (pintype "passive"))
      (node (ref "D111") (pin "2") (pinfunction "K_2") (pintype "passive"))
    )
    (net (code "27") (name "Net-(IC101-BG)") (class "Default")
      (node (ref "IC101") (pin "8") (pinfunction "BG_8") (pintype "passive"))
      (node (ref "TR102") (pin "4") (pinfunction "G_4") (pintype "passive"))
    )
    (net (code "28") (name "Net-(IC101-BOOST)") (class "Default")
      (node (ref "C104") (pin "1") (pinfunction "1_1") (pintype "passive"))
      (node (ref "IC101") (pin "14") (pinfunction "BOOST_14") (pintype "passive"))
    )
    (net (code "29") (name "Net-(IC101-COMP)") (class "Default")
      (node (ref "C107") (pin "1") (pinfunction "1_1") (pintype "passive"))
      (node (ref "IC101") (pin "4") (pinfunction "COMP_4") (pintype "passive"))
    )
    (net (code "30") (name "Net-(IC101-FB)") (class "Default")
      (node (ref "C107") (pin "2") (pinfunction "2_2") (pintype "passive"))
      (node (ref "C145") (pin "2") (pinfunction "2_2") (pintype "passive"))
      (node (ref "IC101") (pin "3") (pinfunction "FB_3") (pintype "passive"))
      (node (ref "R104") (pin "1") (pinfunction "1_1") (pintype "passive"))
      (node (ref "R105") (pin "2") (pinfunction "2_2") (pintype "passive"))
    )
    (net (code "31") (name "Net-(IC101-TG)") (class "Default")
      (node (ref "IC101") (pin "13") (pinfunction "TG_13") (pintype "passive"))
      (node (ref "TR101") (pin "4") (pinfunction "G_4") (pintype "passive"))
    )
    (net (code "32") (name "Net-(IC102-BST)") (class "Default")
      (node (ref "C110") (pin "2") (pinfunction "2_2") (pintype "passive"))
      (node (ref "IC102") (pin "1") (pinfunction "BST_1") (pintype "passive"))
    )
    (net (code "33") (name "Net-(IC102-COMP)") (class "Default")
      (node (ref "C123") (pin "1") (pinfunction "1_1") (pintype "passive"))
      (node (ref "IC102") (pin "6") (pinfunction "COMP_6") (pintype "passive"))
      (node (ref "R113") (pin "2") (pinfunction "2_2") (pintype "passive"))
    )
    (net (code "34") (name "Net-(IC102-FB)") (class "Default")
      (node (ref "C115") (pin "2") (pinfunction "2_2") (pintype "passive"))
      (node (ref "IC102") (pin "5") (pinfunction "FB_5") (pintype "passive"))
      (node (ref "R112") (pin "1") (pinfunction "1_1") (pintype "passive"))
      (node (ref "R114") (pin "2") (pinfunction "2_2") (pintype "passive"))
    )
    (net (code "35") (name "Net-(IC102-SS)") (class "Default")
      (node (ref "C122") (pin "1") (pinfunction "1_1") (pintype "passive"))
      (node (ref "IC102") (pin "4") (pinfunction "SS_4") (pintype "passive"))
    )
    (net (code "36") (name "Net-(IC103-PG)") (class "Default")
      (node (ref "IC103") (pin "2") (pinfunction "PG_2") (pintype "passive"))
      (node (ref "R115") (pin "2") (pinfunction "2_2") (pintype "passive"))
    )
    (net (code "37") (name "Net-(IC104-BST)") (class "Default")
      (node (ref "C127") (pin "2") (pinfunction "2_2") (pintype "passive"))
      (node (ref "IC104") (pin "1") (pinfunction "BST_1") (pintype "passive"))
    )
    (net (code "38") (name "Net-(IC104-COMP)") (class "Default")
      (node (ref "C142") (pin "1") (pinfunction "1_1") (pintype "passive"))
      (node (ref "IC104") (pin "6") (pinfunction "COMP_6") (pintype "passive"))
      (node (ref "R119") (pin "2") (pinfunction "2_2") (pintype "passive"))
    )
    (net (code "39") (name "Net-(IC104-FB)") (class "Default")
      (node (ref "C132") (pin "2") (pinfunction "2_2") (pintype "passive"))
      (node (ref "IC104") (pin "5") (pinfunction "FB_5") (pintype "passive"))
      (node (ref "R118") (pin "1") (pinfunction "1_1") (pintype "passive"))
      (node (ref "R121") (pin "2") (pinfunction "2_2") (pintype "passive"))
    )
    (net (code "40") (name "Net-(IC104-SS)") (class "Default")
      (node (ref "C140") (pin "1") (pinfunction "1_1") (pintype "passive"))
      (node (ref "IC104") (pin "4") (pinfunction "SS_4") (pintype "passive"))
    )
    (net (code "41") (name "Net-(IC105-PG)") (class "Default")
      (node (ref "IC105") (pin "2") (pinfunction "PG_2") (pintype "passive"))
      (node (ref "R120") (pin "2") (pinfunction "2_2") (pintype "passive"))
    )
    (net (code "42") (name "VPWR") (class "Default")
      (node (ref "C105") (pin "1") (pinfunction "1_1") (pintype "passive"))
      (node (ref "C116") (pin "1") (pinfunction "1_1") (pintype "passive"))
      (node (ref "C117") (pin "1") (pinfunction "1_1") (pintype "passive"))
      (node (ref "C118") (pin "1") (pinfunction "1_1") (pintype "passive"))
      (node (ref "C119") (pin "1") (pinfunction "1_1") (pintype "passive"))
      (node (ref "C120") (pin "1") (pinfunction "1_1") (pintype "passive"))
      (node (ref "C121") (pin "1") (pinfunction "1_1") (pintype "passive"))
      (node (ref "C134") (pin "1") (pinfunction "1_1") (pintype "passive"))
      (node (ref "C135") (pin "1") (pinfunction "1_1") (pintype "passive"))
      (node (ref "C136") (pin "1") (pinfunction "1_1") (pintype "passive"))
      (node (ref "C137") (pin "1") (pinfunction "1_1") (pintype "passive"))
      (node (ref "C138") (pin "1") (pinfunction "1_1") (pintype "passive"))
      (node (ref "C139") (pin "1") (pinfunction "1_1") (pintype "passive"))
      (node (ref "C145") (pin "1") (pinfunction "1_1") (pintype "passive"))
      (node (ref "C151") (pin "1") (pinfunction "1_1") (pintype "passive"))
      (node (ref "C152") (pin "1") (pinfunction "1_1") (pintype "passive"))
      (node (ref "C153") (pin "1") (pinfunction "1_1") (pintype "passive"))
      (node (ref "C154") (pin "1") (pinfunction "1_1") (pintype "passive"))
      (node (ref "IC102") (pin "2") (pinfunction "Vin_2") (pintype "passive"))
      (node (ref "IC102") (pin "3") (pinfunction "EN_3") (pintype "passive"))
      (node (ref "IC104") (pin "2") (pinfunction "Vin_2") (pintype "passive"))
      (node (ref "IC104") (pin "3") (pinfunction "EN_3") (pintype "passive"))
      (node (ref "L105") (pin "2") (pinfunction "2_2") (pintype "passive"))
      (node (ref "R104") (pin "2") (pinfunction "2_2") (pintype "passive"))
    )
  )
)
